# Frontboard.net
KiCad netlist of a schematic drawn in EAGLE
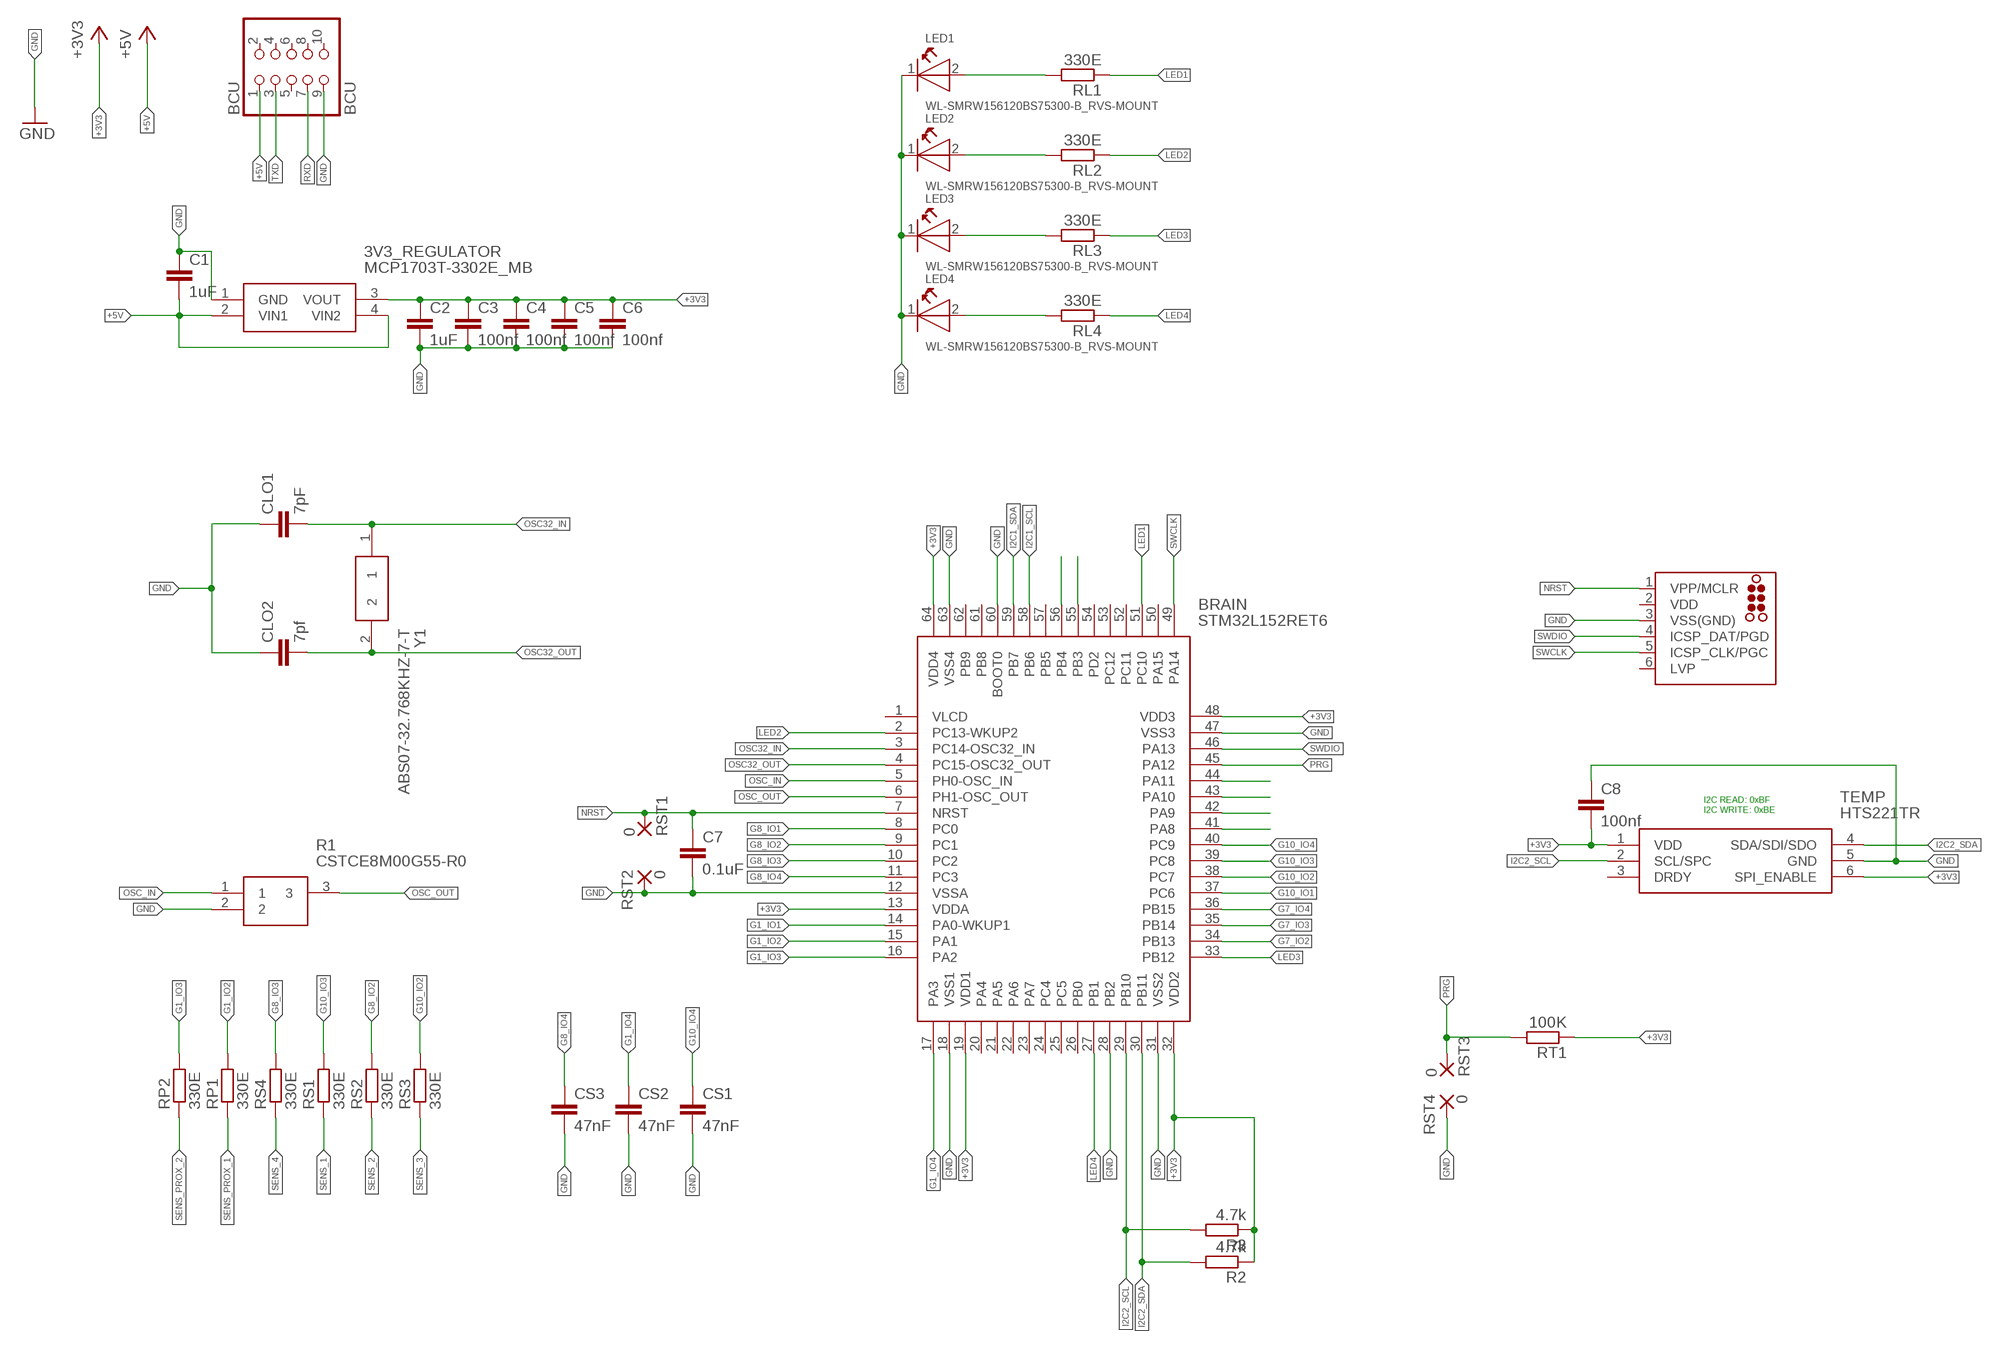
[diagram p0: schematic, sheet 1]

(export (version "E")
  (design (tool "Eeschema 10.0.6"))
  (components
    (comp (ref "3V3_REGULATOR")
      (value "MCP1703T-3302E_MB")
      (footprint "eagle-import:SOT-89(MB)")
      (fields
        (field (name "ARROW_PART_NUMBER") "MCP1703T-3302E/MB")
        (field (name "RS_PART_NUMBER") "9122916")
      )
      (libsource (lib "eagle-import") (part "MCP1703T-3302E_MB"))
    )
    (comp (ref "BCU")
      (value "BCU")
      (footprint "eagle-import:2X05SMD")
      (libsource (lib "eagle-import") (part "PINHD-2X5_2.54-SMD"))
    )
    (comp (ref "BRAIN")
      (value "STM32L152RET6")
      (footprint "eagle-import:QFP50P1200X1200X160-64N")
      (libsource (lib "eagle-import") (part "STM32L152RET6"))
    )
    (comp (ref "C1")
      (value "1uF")
      (footprint "eagle-import:C0603")
      (libsource (lib "eagle-import") (part "C-EUC0603"))
    )
    (comp (ref "C2")
      (value "1uF")
      (footprint "eagle-import:C0603")
      (libsource (lib "eagle-import") (part "C-EUC0603"))
    )
    (comp (ref "C3")
      (value "100nf")
      (footprint "eagle-import:C0603")
      (libsource (lib "eagle-import") (part "C-EUC0603"))
    )
    (comp (ref "C4")
      (value "100nf")
      (footprint "eagle-import:C0603")
      (libsource (lib "eagle-import") (part "C-EUC0603"))
    )
    (comp (ref "C5")
      (value "100nf")
      (footprint "eagle-import:C0603")
      (libsource (lib "eagle-import") (part "C-EUC0603"))
    )
    (comp (ref "C6")
      (value "100nf")
      (footprint "eagle-import:C0603")
      (libsource (lib "eagle-import") (part "C-EUC0603"))
    )
    (comp (ref "C7")
      (value "0.1uF")
      (footprint "eagle-import:C0603")
      (libsource (lib "eagle-import") (part "C-EUC0603"))
    )
    (comp (ref "C8")
      (value "100nf")
      (footprint "eagle-import:C0603")
      (libsource (lib "eagle-import") (part "C-EUC0603"))
    )
    (comp (ref "CLO1")
      (value "7pF")
      (footprint "eagle-import:C0603")
      (libsource (lib "eagle-import") (part "C-EUC0603"))
    )
    (comp (ref "CLO2")
      (value "7pf")
      (footprint "eagle-import:C0603")
      (libsource (lib "eagle-import") (part "C-EUC0603"))
    )
    (comp (ref "CS1")
      (value "47nF")
      (footprint "eagle-import:C0603")
      (libsource (lib "eagle-import") (part "C-EUC0603"))
    )
    (comp (ref "CS2")
      (value "47nF")
      (footprint "eagle-import:C0603")
      (libsource (lib "eagle-import") (part "C-EUC0603"))
    )
    (comp (ref "CS3")
      (value "47nF")
      (footprint "eagle-import:C0603")
      (libsource (lib "eagle-import") (part "C-EUC0603"))
    )
    (comp (ref "LED1")
      (value "WL-SMRW156120BS75300-B_RVS-MOUNT")
      (footprint "eagle-import:WL-SMRW-1206-CYLDR-REVERSE-MOUNT")
      (libsource (lib "eagle-import") (part "WL-SMRW156120BS75300-B_RVS-MOUNT"))
    )
    (comp (ref "LED2")
      (value "WL-SMRW156120BS75300-B_RVS-MOUNT")
      (footprint "eagle-import:WL-SMRW-1206-CYLDR-REVERSE-MOUNT")
      (libsource (lib "eagle-import") (part "WL-SMRW156120BS75300-B_RVS-MOUNT"))
    )
    (comp (ref "LED3")
      (value "WL-SMRW156120BS75300-B_RVS-MOUNT")
      (footprint "eagle-import:WL-SMRW-1206-CYLDR-REVERSE-MOUNT")
      (libsource (lib "eagle-import") (part "WL-SMRW156120BS75300-B_RVS-MOUNT"))
    )
    (comp (ref "LED4")
      (value "WL-SMRW156120BS75300-B_RVS-MOUNT")
      (footprint "eagle-import:WL-SMRW-1206-CYLDR-REVERSE-MOUNT")
      (libsource (lib "eagle-import") (part "WL-SMRW156120BS75300-B_RVS-MOUNT"))
    )
    (comp (ref "R1")
      (value "CSTCE8M00G55-R0")
      (footprint "eagle-import:CSTCE12M0G55-R0")
      (fields (field (name "RS_PART_NUMBER") "7214821P"))
      (libsource (lib "eagle-import") (part "CSTCE8M00G55-R0"))
    )
    (comp (ref "R2")
      (value "4.7k")
      (footprint "eagle-import:R0603")
      (libsource (lib "eagle-import") (part "R-EU_R0603"))
    )
    (comp (ref "R3")
      (value "4.7k")
      (footprint "eagle-import:R0603")
      (libsource (lib "eagle-import") (part "R-EU_R0603"))
    )
    (comp (ref "RL1")
      (value "330E")
      (footprint "eagle-import:R0603")
      (libsource (lib "eagle-import") (part "R-EU_R0603"))
    )
    (comp (ref "RL2")
      (value "330E")
      (footprint "eagle-import:R0603")
      (libsource (lib "eagle-import") (part "R-EU_R0603"))
    )
    (comp (ref "RL3")
      (value "330E")
      (footprint "eagle-import:R0603")
      (libsource (lib "eagle-import") (part "R-EU_R0603"))
    )
    (comp (ref "RL4")
      (value "330E")
      (footprint "eagle-import:R0603")
      (libsource (lib "eagle-import") (part "R-EU_R0603"))
    )
    (comp (ref "RP1")
      (value "330E")
      (footprint "eagle-import:R0603")
      (libsource (lib "eagle-import") (part "R-EU_R0603"))
    )
    (comp (ref "RP2")
      (value "330E")
      (footprint "eagle-import:R0603")
      (libsource (lib "eagle-import") (part "R-EU_R0603"))
    )
    (comp (ref "RS1")
      (value "330E")
      (footprint "eagle-import:R0603")
      (libsource (lib "eagle-import") (part "R-EU_R0603"))
    )
    (comp (ref "RS2")
      (value "330E")
      (footprint "eagle-import:R0603")
      (libsource (lib "eagle-import") (part "R-EU_R0603"))
    )
    (comp (ref "RS3")
      (value "330E")
      (footprint "eagle-import:R0603")
      (libsource (lib "eagle-import") (part "R-EU_R0603"))
    )
    (comp (ref "RS4")
      (value "330E")
      (footprint "eagle-import:R0603")
      (libsource (lib "eagle-import") (part "R-EU_R0603"))
    )
    (comp (ref "RST1")
      (value "0")
      (footprint "eagle-import:SMD2,54-5,08")
      (libsource (lib "eagle-import") (part "SMD5"))
    )
    (comp (ref "RST2")
      (value "0")
      (footprint "eagle-import:SMD2,54-5,08")
      (libsource (lib "eagle-import") (part "SMD5"))
    )
    (comp (ref "RST3")
      (value "0")
      (footprint "eagle-import:SMD2,54-5,08")
      (libsource (lib "eagle-import") (part "SMD5"))
    )
    (comp (ref "RST4")
      (value "0")
      (footprint "eagle-import:SMD2,54-5,08")
      (libsource (lib "eagle-import") (part "SMD5"))
    )
    (comp (ref "RT1")
      (value "100K")
      (footprint "eagle-import:R0603")
      (libsource (lib "eagle-import") (part "R-EU_R0603"))
    )
    (comp (ref "SWD")
      (value "SWD")
      (footprint "eagle-import:TC2030-MCP-NL")
      (libsource (lib "eagle-import") (part "TC2030-MCP-NL"))
    )
    (comp (ref "TEMP")
      (value "HTS221TR")
      (footprint "eagle-import:HLGA-6L")
      (fields (field (name "RS_PART_NUMBER") "1660935"))
      (libsource (lib "eagle-import") (part "HTS221TR"))
    )
    (comp (ref "Y1")
      (value "ABS07-32.768KHZ-7-T")
      (footprint "eagle-import:ABS-07")
      (fields (field (name "RS_PART_NUMBER") "1712773P"))
      (libsource (lib "eagle-import") (part "ABS07-32.768KHZ-7-T"))
    )
  )
  (nets
    (net (code "1") (name "+3V3") (class "Default")
      (node (ref "3V3_REGULATOR") (pin "3") (pinfunction "VOUT_3") (pintype "bidirectional"))
      (node (ref "BRAIN") (pin "13") (pinfunction "VDDA_13") (pintype "power_in"))
      (node (ref "BRAIN") (pin "19") (pinfunction "VDD1_19") (pintype "power_in"))
      (node (ref "BRAIN") (pin "32") (pinfunction "VDD2_32") (pintype "power_in"))
      (node (ref "BRAIN") (pin "48") (pinfunction "VDD3_48") (pintype "power_in"))
      (node (ref "BRAIN") (pin "64") (pinfunction "VDD4_64") (pintype "power_in"))
      (node (ref "C2") (pin "1") (pinfunction "1_1") (pintype "passive"))
      (node (ref "C3") (pin "1") (pinfunction "1_1") (pintype "passive"))
      (node (ref "C4") (pin "1") (pinfunction "1_1") (pintype "passive"))
      (node (ref "C5") (pin "1") (pinfunction "1_1") (pintype "passive"))
      (node (ref "C6") (pin "1") (pinfunction "1_1") (pintype "passive"))
      (node (ref "C8") (pin "2") (pinfunction "2_2") (pintype "passive"))
      (node (ref "R2") (pin "1") (pinfunction "1_1") (pintype "passive"))
      (node (ref "R3") (pin "1") (pinfunction "1_1") (pintype "passive"))
      (node (ref "RT1") (pin "1") (pinfunction "1_1") (pintype "passive"))
      (node (ref "TEMP") (pin "1") (pinfunction "VDD_1") (pintype "bidirectional"))
      (node (ref "TEMP") (pin "6") (pinfunction "SPI_ENABLE_6") (pintype "bidirectional"))
    )
    (net (code "2") (name "+5V") (class "Default")
      (node (ref "3V3_REGULATOR") (pin "2") (pinfunction "VIN1_2") (pintype "bidirectional"))
      (node (ref "3V3_REGULATOR") (pin "4") (pinfunction "VIN2_4") (pintype "bidirectional"))
      (node (ref "BCU") (pin "1") (pinfunction "1_1") (pintype "passive"))
      (node (ref "C1") (pin "2") (pinfunction "2_2") (pintype "passive"))
    )
    (net (code "3") (name "/VDD") (class "Default")
      (node (ref "SWD") (pin "2") (pinfunction "VDD_2") (pintype "power_in"))
    )
    (net (code "4") (name "/VLCD") (class "Default")
      (node (ref "BRAIN") (pin "1") (pinfunction "VLCD_1") (pintype "power_in"))
    )
    (net (code "5") (name "G1_IO1") (class "Default")
      (node (ref "BRAIN") (pin "14") (pinfunction "PA0-WKUP1_14") (pintype "bidirectional"))
    )
    (net (code "6") (name "G1_IO2") (class "Default")
      (node (ref "BRAIN") (pin "15") (pinfunction "PA1_15") (pintype "bidirectional"))
      (node (ref "RP1") (pin "2") (pinfunction "2_2") (pintype "passive"))
    )
    (net (code "7") (name "G1_IO3") (class "Default")
      (node (ref "BRAIN") (pin "16") (pinfunction "PA2_16") (pintype "bidirectional"))
      (node (ref "RP2") (pin "2") (pinfunction "2_2") (pintype "passive"))
    )
    (net (code "8") (name "G1_IO4") (class "Default")
      (node (ref "BRAIN") (pin "17") (pinfunction "PA3_17") (pintype "bidirectional"))
      (node (ref "CS2") (pin "1") (pinfunction "1_1") (pintype "passive"))
    )
    (net (code "9") (name "G7_IO2") (class "Default")
      (node (ref "BRAIN") (pin "34") (pinfunction "PB13_34") (pintype "bidirectional"))
    )
    (net (code "10") (name "G7_IO3") (class "Default")
      (node (ref "BRAIN") (pin "35") (pinfunction "PB14_35") (pintype "bidirectional"))
    )
    (net (code "11") (name "G7_IO4") (class "Default")
      (node (ref "BRAIN") (pin "36") (pinfunction "PB15_36") (pintype "bidirectional"))
    )
    (net (code "12") (name "G8_IO1") (class "Default")
      (node (ref "BRAIN") (pin "8") (pinfunction "PC0_8") (pintype "bidirectional"))
    )
    (net (code "13") (name "G8_IO2") (class "Default")
      (node (ref "BRAIN") (pin "9") (pinfunction "PC1_9") (pintype "bidirectional"))
      (node (ref "RS2") (pin "2") (pinfunction "2_2") (pintype "passive"))
    )
    (net (code "14") (name "G8_IO3") (class "Default")
      (node (ref "BRAIN") (pin "10") (pinfunction "PC2_10") (pintype "bidirectional"))
      (node (ref "RS4") (pin "2") (pinfunction "2_2") (pintype "passive"))
    )
    (net (code "15") (name "G8_IO4") (class "Default")
      (node (ref "BRAIN") (pin "11") (pinfunction "PC3_11") (pintype "bidirectional"))
      (node (ref "CS3") (pin "1") (pinfunction "1_1") (pintype "passive"))
    )
    (net (code "16") (name "G10_IO1") (class "Default")
      (node (ref "BRAIN") (pin "37") (pinfunction "PC6_37") (pintype "bidirectional"))
    )
    (net (code "17") (name "G10_IO2") (class "Default")
      (node (ref "BRAIN") (pin "38") (pinfunction "PC7_38") (pintype "bidirectional"))
      (node (ref "RS3") (pin "2") (pinfunction "2_2") (pintype "passive"))
    )
    (net (code "18") (name "G10_IO3") (class "Default")
      (node (ref "BRAIN") (pin "39") (pinfunction "PC8_39") (pintype "bidirectional"))
      (node (ref "RS1") (pin "2") (pinfunction "2_2") (pintype "passive"))
    )
    (net (code "19") (name "G10_IO4") (class "Default")
      (node (ref "BRAIN") (pin "40") (pinfunction "PC9_40") (pintype "bidirectional"))
      (node (ref "CS1") (pin "1") (pinfunction "1_1") (pintype "passive"))
    )
    (net (code "20") (name "GND") (class "Default")
      (node (ref "3V3_REGULATOR") (pin "1") (pinfunction "GND_1") (pintype "bidirectional"))
      (node (ref "BCU") (pin "9") (pinfunction "9_9") (pintype "passive"))
      (node (ref "BRAIN") (pin "12") (pinfunction "VSSA_12") (pintype "power_in"))
      (node (ref "BRAIN") (pin "18") (pinfunction "VSS1_18") (pintype "power_in"))
      (node (ref "BRAIN") (pin "28") (pinfunction "PB2_28") (pintype "bidirectional"))
      (node (ref "BRAIN") (pin "31") (pinfunction "VSS2_31") (pintype "power_in"))
      (node (ref "BRAIN") (pin "47") (pinfunction "VSS3_47") (pintype "power_in"))
      (node (ref "BRAIN") (pin "60") (pinfunction "BOOT0_60") (pintype "bidirectional"))
      (node (ref "BRAIN") (pin "63") (pinfunction "VSS4_63") (pintype "power_in"))
      (node (ref "C1") (pin "1") (pinfunction "1_1") (pintype "passive"))
      (node (ref "C2") (pin "2") (pinfunction "2_2") (pintype "passive"))
      (node (ref "C3") (pin "2") (pinfunction "2_2") (pintype "passive"))
      (node (ref "C4") (pin "2") (pinfunction "2_2") (pintype "passive"))
      (node (ref "C5") (pin "2") (pinfunction "2_2") (pintype "passive"))
      (node (ref "C6") (pin "2") (pinfunction "2_2") (pintype "passive"))
      (node (ref "C7") (pin "2") (pinfunction "2_2") (pintype "passive"))
      (node (ref "C8") (pin "1") (pinfunction "1_1") (pintype "passive"))
      (node (ref "CLO1") (pin "1") (pinfunction "1_1") (pintype "passive"))
      (node (ref "CLO2") (pin "1") (pinfunction "1_1") (pintype "passive"))
      (node (ref "CS1") (pin "2") (pinfunction "2_2") (pintype "passive"))
      (node (ref "CS2") (pin "2") (pinfunction "2_2") (pintype "passive"))
      (node (ref "CS3") (pin "2") (pinfunction "2_2") (pintype "passive"))
      (node (ref "LED1") (pin "1") (pinfunction "K_1") (pintype "bidirectional"))
      (node (ref "LED2") (pin "1") (pinfunction "K_1") (pintype "bidirectional"))
      (node (ref "LED3") (pin "1") (pinfunction "K_1") (pintype "bidirectional"))
      (node (ref "LED4") (pin "1") (pinfunction "K_1") (pintype "bidirectional"))
      (node (ref "R1") (pin "2") (pinfunction "2_2") (pintype "bidirectional"))
      (node (ref "RST2") (pin "1") (pinfunction "P_1") (pintype "passive"))
      (node (ref "RST4") (pin "1") (pinfunction "P_1") (pintype "passive"))
      (node (ref "SWD") (pin "3") (pinfunction "VSS(GND)_3") (pintype "power_in"))
      (node (ref "TEMP") (pin "5") (pinfunction "GND_5") (pintype "bidirectional"))
    )
    (net (code "21") (name "I2C1_SCL") (class "Default")
      (node (ref "BRAIN") (pin "58") (pinfunction "PB6_58") (pintype "bidirectional"))
    )
    (net (code "22") (name "I2C1_SDA") (class "Default")
      (node (ref "BRAIN") (pin "59") (pinfunction "PB7_59") (pintype "bidirectional"))
    )
    (net (code "23") (name "I2C2_SCL") (class "Default")
      (node (ref "BRAIN") (pin "29") (pinfunction "PB10_29") (pintype "bidirectional"))
      (node (ref "R3") (pin "2") (pinfunction "2_2") (pintype "passive"))
      (node (ref "TEMP") (pin "2") (pinfunction "SCL/SPC_2") (pintype "bidirectional"))
    )
    (net (code "24") (name "I2C2_SDA") (class "Default")
      (node (ref "BRAIN") (pin "30") (pinfunction "PB11_30") (pintype "bidirectional"))
      (node (ref "R2") (pin "2") (pinfunction "2_2") (pintype "passive"))
      (node (ref "TEMP") (pin "4") (pinfunction "SDA/SDI/SDO_4") (pintype "bidirectional"))
    )
    (net (code "25") (name "LED1") (class "Default")
      (node (ref "BRAIN") (pin "51") (pinfunction "PC10_51") (pintype "bidirectional"))
      (node (ref "RL1") (pin "1") (pinfunction "1_1") (pintype "passive"))
    )
    (net (code "26") (name "LED2") (class "Default")
      (node (ref "BRAIN") (pin "2") (pinfunction "PC13-WKUP2_2") (pintype "bidirectional"))
      (node (ref "RL2") (pin "1") (pinfunction "1_1") (pintype "passive"))
    )
    (net (code "27") (name "LED3") (class "Default")
      (node (ref "BRAIN") (pin "33") (pinfunction "PB12_33") (pintype "bidirectional"))
      (node (ref "RL3") (pin "1") (pinfunction "1_1") (pintype "passive"))
    )
    (net (code "28") (name "LED4") (class "Default")
      (node (ref "BRAIN") (pin "27") (pinfunction "PB1_27") (pintype "bidirectional"))
      (node (ref "RL4") (pin "1") (pinfunction "1_1") (pintype "passive"))
    )
    (net (code "29") (name "NRST") (class "Default")
      (node (ref "BRAIN") (pin "7") (pinfunction "NRST_7") (pintype "bidirectional"))
      (node (ref "C7") (pin "1") (pinfunction "1_1") (pintype "passive"))
      (node (ref "RST1") (pin "1") (pinfunction "P_1") (pintype "passive"))
      (node (ref "SWD") (pin "1") (pinfunction "VPP/MCLR_1") (pintype "passive"))
    )
    (net (code "30") (name "Net-(LED1-A)") (class "Default")
      (node (ref "LED1") (pin "2") (pinfunction "A_2") (pintype "bidirectional"))
      (node (ref "RL1") (pin "2") (pinfunction "2_2") (pintype "passive"))
    )
    (net (code "31") (name "Net-(LED2-A)") (class "Default")
      (node (ref "LED2") (pin "2") (pinfunction "A_2") (pintype "bidirectional"))
      (node (ref "RL2") (pin "2") (pinfunction "2_2") (pintype "passive"))
    )
    (net (code "32") (name "Net-(LED3-A)") (class "Default")
      (node (ref "LED3") (pin "2") (pinfunction "A_2") (pintype "bidirectional"))
      (node (ref "RL3") (pin "2") (pinfunction "2_2") (pintype "passive"))
    )
    (net (code "33") (name "Net-(LED4-A)") (class "Default")
      (node (ref "LED4") (pin "2") (pinfunction "A_2") (pintype "bidirectional"))
      (node (ref "RL4") (pin "2") (pinfunction "2_2") (pintype "passive"))
    )
    (net (code "34") (name "OSC32_IN") (class "Default")
      (node (ref "BRAIN") (pin "3") (pinfunction "PC14-OSC32_IN_3") (pintype "bidirectional"))
      (node (ref "CLO1") (pin "2") (pinfunction "2_2") (pintype "passive"))
      (node (ref "Y1") (pin "1") (pinfunction "1_1") (pintype "bidirectional"))
    )
    (net (code "35") (name "OSC32_OUT") (class "Default")
      (node (ref "BRAIN") (pin "4") (pinfunction "PC15-OSC32_OUT_4") (pintype "bidirectional"))
      (node (ref "CLO2") (pin "2") (pinfunction "2_2") (pintype "passive"))
      (node (ref "Y1") (pin "2") (pinfunction "2_2") (pintype "bidirectional"))
    )
    (net (code "36") (name "OSC_IN") (class "Default")
      (node (ref "BRAIN") (pin "5") (pinfunction "PH0-OSC_IN_5") (pintype "bidirectional"))
      (node (ref "R1") (pin "1") (pinfunction "1_1") (pintype "bidirectional"))
    )
    (net (code "37") (name "OSC_OUT") (class "Default")
      (node (ref "BRAIN") (pin "6") (pinfunction "PH1-OSC_OUT_6") (pintype "bidirectional"))
      (node (ref "R1") (pin "3") (pinfunction "3_3") (pintype "bidirectional"))
    )
    (net (code "38") (name "PRG") (class "Default")
      (node (ref "BRAIN") (pin "45") (pinfunction "PA12_45") (pintype "bidirectional"))
      (node (ref "RST3") (pin "1") (pinfunction "P_1") (pintype "passive"))
      (node (ref "RT1") (pin "2") (pinfunction "2_2") (pintype "passive"))
    )
    (net (code "39") (name "RXD") (class "Default")
      (node (ref "BCU") (pin "7") (pinfunction "7_7") (pintype "passive"))
    )
    (net (code "40") (name "SENS_1") (class "Default")
      (node (ref "RS1") (pin "1") (pinfunction "1_1") (pintype "passive"))
    )
    (net (code "41") (name "SENS_2") (class "Default")
      (node (ref "RS2") (pin "1") (pinfunction "1_1") (pintype "passive"))
    )
    (net (code "42") (name "SENS_3") (class "Default")
      (node (ref "RS3") (pin "1") (pinfunction "1_1") (pintype "passive"))
    )
    (net (code "43") (name "SENS_4") (class "Default")
      (node (ref "RS4") (pin "1") (pinfunction "1_1") (pintype "passive"))
    )
    (net (code "44") (name "SENS_PROX_1") (class "Default")
      (node (ref "RP1") (pin "1") (pinfunction "1_1") (pintype "passive"))
    )
    (net (code "45") (name "SENS_PROX_2") (class "Default")
      (node (ref "RP2") (pin "1") (pinfunction "1_1") (pintype "passive"))
    )
    (net (code "46") (name "SWCLK") (class "Default")
      (node (ref "BRAIN") (pin "49") (pinfunction "PA14_49") (pintype "bidirectional"))
      (node (ref "SWD") (pin "5") (pinfunction "ICSP_CLK/PGC_5") (pintype "output"))
    )
    (net (code "47") (name "SWDIO") (class "Default")
      (node (ref "BRAIN") (pin "46") (pinfunction "PA13_46") (pintype "bidirectional"))
      (node (ref "SWD") (pin "4") (pinfunction "ICSP_DAT/PGD_4") (pintype "bidirectional"))
    )
    (net (code "48") (name "TXD") (class "Default")
      (node (ref "BCU") (pin "3") (pinfunction "3_3") (pintype "passive"))
    )
    (net (code "49") (name "unconnected-(BCU-Pad2)") (class "Default")
      (node (ref "BCU") (pin "2") (pinfunction "2_2") (pintype "passive"))
    )
    (net (code "50") (name "unconnected-(BCU-Pad4)") (class "Default")
      (node (ref "BCU") (pin "4") (pinfunction "4_4") (pintype "passive"))
    )
    (net (code "51") (name "unconnected-(BCU-Pad5)") (class "Default")
      (node (ref "BCU") (pin "5") (pinfunction "5_5") (pintype "passive"))
    )
    (net (code "52") (name "unconnected-(BCU-Pad6)") (class "Default")
      (node (ref "BCU") (pin "6") (pinfunction "6_6") (pintype "passive"))
    )
    (net (code "53") (name "unconnected-(BCU-Pad8)") (class "Default")
      (node (ref "BCU") (pin "8") (pinfunction "8_8") (pintype "passive"))
    )
    (net (code "54") (name "unconnected-(BCU-Pad10)") (class "Default")
      (node (ref "BCU") (pin "10") (pinfunction "10_10") (pintype "passive"))
    )
    (net (code "55") (name "unconnected-(BRAIN-PA4-Pad20)") (class "Default")
      (node (ref "BRAIN") (pin "20") (pinfunction "PA4_20") (pintype "bidirectional"))
    )
    (net (code "56") (name "unconnected-(BRAIN-PA5-Pad21)") (class "Default")
      (node (ref "BRAIN") (pin "21") (pinfunction "PA5_21") (pintype "bidirectional"))
    )
    (net (code "57") (name "unconnected-(BRAIN-PA6-Pad22)") (class "Default")
      (node (ref "BRAIN") (pin "22") (pinfunction "PA6_22") (pintype "bidirectional"))
    )
    (net (code "58") (name "unconnected-(BRAIN-PA7-Pad23)") (class "Default")
      (node (ref "BRAIN") (pin "23") (pinfunction "PA7_23") (pintype "bidirectional"))
    )
    (net (code "59") (name "unconnected-(BRAIN-PA8-Pad41)") (class "Default")
      (node (ref "BRAIN") (pin "41") (pinfunction "PA8_41") (pintype "bidirectional"))
    )
    (net (code "60") (name "unconnected-(BRAIN-PA9-Pad42)") (class "Default")
      (node (ref "BRAIN") (pin "42") (pinfunction "PA9_42") (pintype "bidirectional"))
    )
    (net (code "61") (name "unconnected-(BRAIN-PA10-Pad43)") (class "Default")
      (node (ref "BRAIN") (pin "43") (pinfunction "PA10_43") (pintype "bidirectional"))
    )
    (net (code "62") (name "unconnected-(BRAIN-PA11-Pad44)") (class "Default")
      (node (ref "BRAIN") (pin "44") (pinfunction "PA11_44") (pintype "bidirectional"))
    )
    (net (code "63") (name "unconnected-(BRAIN-PA15-Pad50)") (class "Default")
      (node (ref "BRAIN") (pin "50") (pinfunction "PA15_50") (pintype "bidirectional"))
    )
    (net (code "64") (name "unconnected-(BRAIN-PB0-Pad26)") (class "Default")
      (node (ref "BRAIN") (pin "26") (pinfunction "PB0_26") (pintype "bidirectional"))
    )
    (net (code "65") (name "unconnected-(BRAIN-PB3-Pad55)") (class "Default")
      (node (ref "BRAIN") (pin "55") (pinfunction "PB3_55") (pintype "bidirectional"))
    )
    (net (code "66") (name "unconnected-(BRAIN-PB4-Pad56)") (class "Default")
      (node (ref "BRAIN") (pin "56") (pinfunction "PB4_56") (pintype "bidirectional"))
    )
    (net (code "67") (name "unconnected-(BRAIN-PB5-Pad57)") (class "Default")
      (node (ref "BRAIN") (pin "57") (pinfunction "PB5_57") (pintype "bidirectional"))
    )
    (net (code "68") (name "unconnected-(BRAIN-PB8-Pad61)") (class "Default")
      (node (ref "BRAIN") (pin "61") (pinfunction "PB8_61") (pintype "bidirectional"))
    )
    (net (code "69") (name "unconnected-(BRAIN-PB9-Pad62)") (class "Default")
      (node (ref "BRAIN") (pin "62") (pinfunction "PB9_62") (pintype "bidirectional"))
    )
    (net (code "70") (name "unconnected-(BRAIN-PC4-Pad24)") (class "Default")
      (node (ref "BRAIN") (pin "24") (pinfunction "PC4_24") (pintype "bidirectional"))
    )
    (net (code "71") (name "unconnected-(BRAIN-PC5-Pad25)") (class "Default")
      (node (ref "BRAIN") (pin "25") (pinfunction "PC5_25") (pintype "bidirectional"))
    )
    (net (code "72") (name "unconnected-(BRAIN-PC11-Pad52)") (class "Default")
      (node (ref "BRAIN") (pin "52") (pinfunction "PC11_52") (pintype "bidirectional"))
    )
    (net (code "73") (name "unconnected-(BRAIN-PC12-Pad53)") (class "Default")
      (node (ref "BRAIN") (pin "53") (pinfunction "PC12_53") (pintype "bidirectional"))
    )
    (net (code "74") (name "unconnected-(BRAIN-PD2-Pad54)") (class "Default")
      (node (ref "BRAIN") (pin "54") (pinfunction "PD2_54") (pintype "bidirectional"))
    )
    (net (code "75") (name "unconnected-(SWD-LVP-Pad6)") (class "Default")
      (node (ref "SWD") (pin "6") (pinfunction "LVP_6") (pintype "bidirectional"))
    )
    (net (code "76") (name "unconnected-(TEMP-DRDY-Pad3)") (class "Default")
      (node (ref "TEMP") (pin "3") (pinfunction "DRDY_3") (pintype "bidirectional"))
    )
  )
)
